# Handshake.net
KiCad netlist of a schematic drawn in Altium Designer
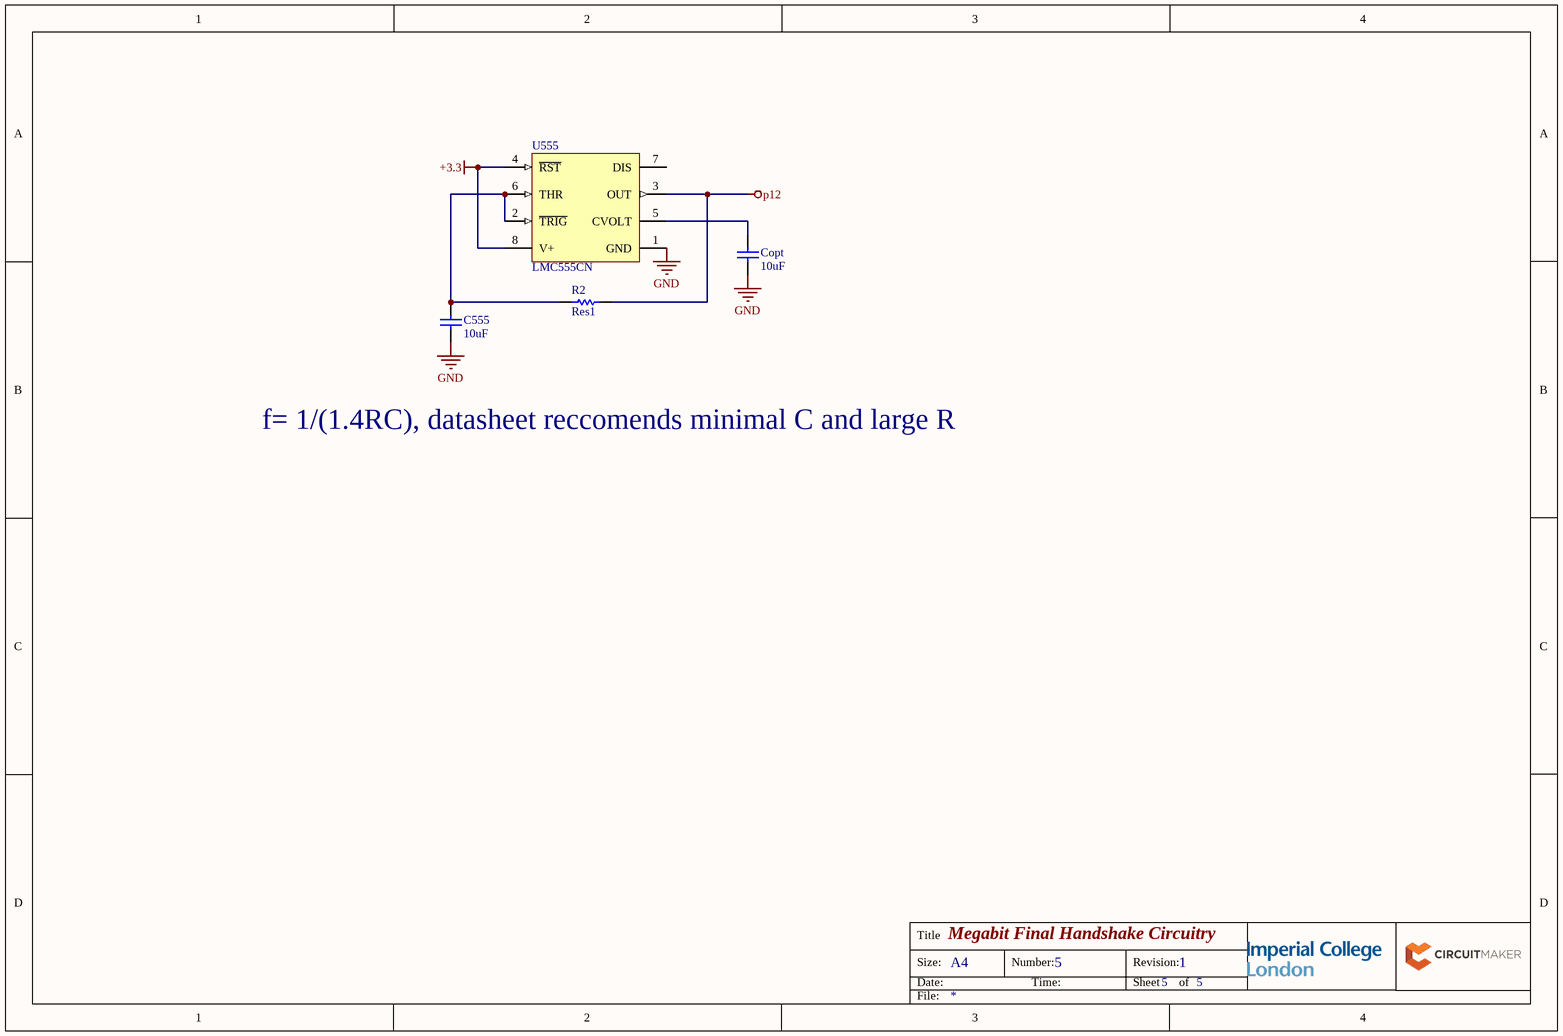
[diagram p0: Handshake.SchDoc]

(export (version "E")
  (design (tool "Eeschema 10.0.6"))
  (components
    (comp (ref "C555")
      (value "10uF")
      (footprint "Vishay K104K15X7RF5TL2")
      (description "K Series 100nF 50 V ±10 % Tolerance X7R Radial Multilayer Ceramic Capacitor")
      (fields (field (name "MANUFACTURER PART NUMBER") "K104K15X7RF5TL2"))
      (libsource (lib "CommunityVault") (part "CMP-124240-16"))
    )
    (comp (ref "Copt")
      (value "10uF")
      (footprint "Vishay K104K15X7RF5TL2")
      (description "K Series 100nF 50 V ±10 % Tolerance X7R Radial Multilayer Ceramic Capacitor")
      (fields (field (name "MANUFACTURER PART NUMBER") "K104K15X7RF5TL2"))
      (libsource (lib "CommunityVault") (part "CMP-124240-16"))
    )
    (comp (ref "R2")
      (value "Res1")
      (footprint "PCB-3613466-1")
      (description "Resistor 0.25W")
      (libsource (lib "CommunityVault") (part "SYM-b15c796618a36e9b-1"))
    )
    (comp (ref "U555")
      (value "LMC555CN")
      (footprint "N08E")
      (description "CMOS Timer, 8-pin MDIP")
      (libsource (lib "CommunityVault") (part "AN-TIMER-LMC555-8"))
    )
  )
  (nets
    (net (code "1") (name "+3.3") (class "Default")
      (node (ref "U555") (pin "4") (pinfunction "~{RST}_4") (pintype "input"))
      (node (ref "U555") (pin "8") (pinfunction "V+_8") (pintype "power_in"))
    )
    (net (code "2") (name "GND") (class "Default")
      (node (ref "C555") (pin "1") (pinfunction "1_1") (pintype "passive"))
      (node (ref "Copt") (pin "1") (pinfunction "1_1") (pintype "passive"))
      (node (ref "U555") (pin "1") (pinfunction "GND_1") (pintype "power_in"))
    )
    (net (code "3") (name "Net-(U555-CVOLT)") (class "Default")
      (node (ref "Copt") (pin "2") (pinfunction "2_2") (pintype "passive"))
      (node (ref "U555") (pin "5") (pinfunction "CVOLT_5") (pintype "passive"))
    )
    (net (code "4") (name "Net-(U555-THR)") (class "Default")
      (node (ref "C555") (pin "2") (pinfunction "2_2") (pintype "passive"))
      (node (ref "R2") (pin "2") (pinfunction "2_2") (pintype "passive"))
      (node (ref "U555") (pin "2") (pinfunction "~{TRIG}_2") (pintype "input"))
      (node (ref "U555") (pin "6") (pinfunction "THR_6") (pintype "input"))
    )
    (net (code "5") (name "p12") (class "Default")
      (node (ref "R2") (pin "1") (pinfunction "1_1") (pintype "passive"))
      (node (ref "U555") (pin "3") (pinfunction "OUT_3") (pintype "output"))
    )
    (net (code "6") (name "unconnected-(U555-DIS-Pad7)") (class "Default")
      (node (ref "U555") (pin "7") (pinfunction "DIS_7") (pintype "open_collector"))
    )
  )
)
